# sticky-watch-v1_4.net
KiCad netlist of a schematic drawn in EAGLE
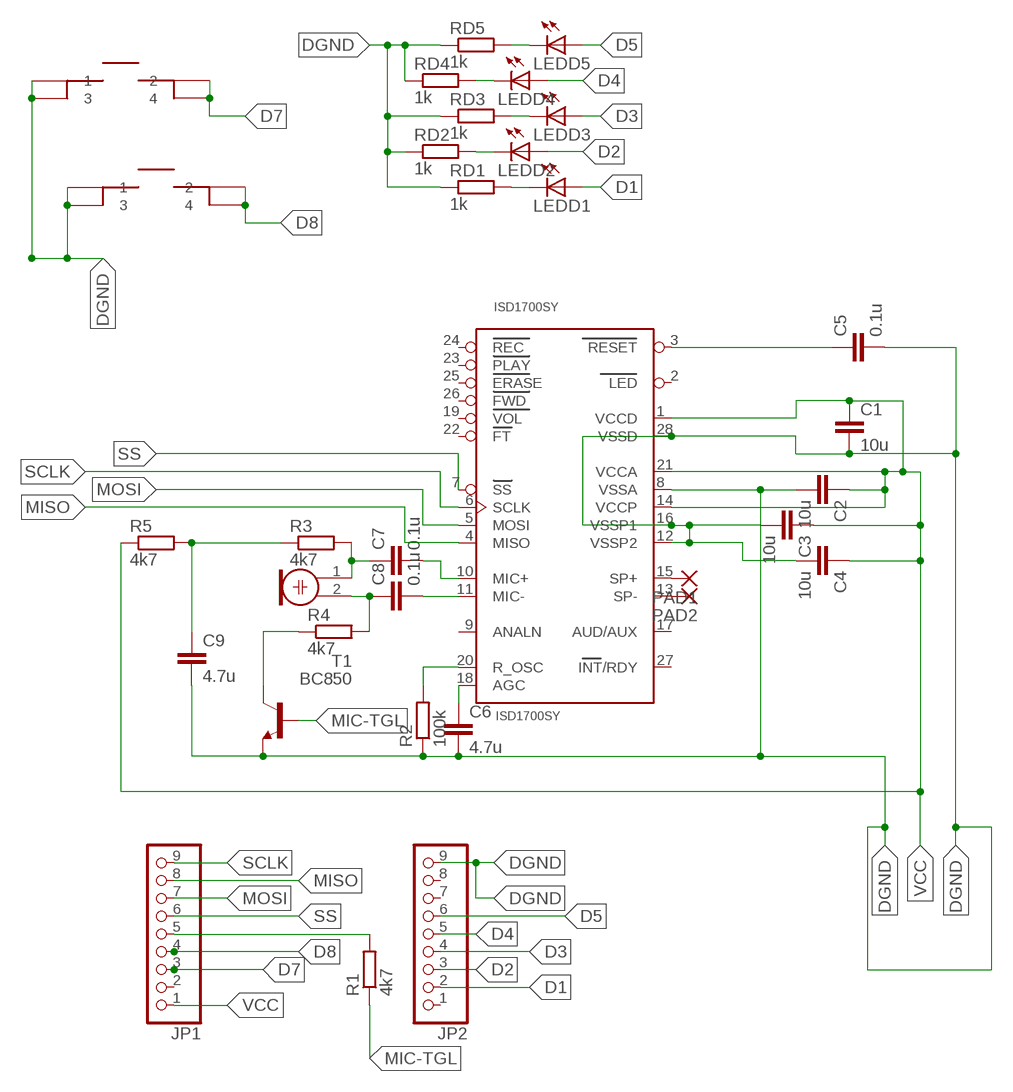
[diagram p0: schematic, sheet 1]

(export (version "E")
  (design (tool "Eeschema 10.0.6"))
  (components
    (comp (ref "C1")
      (value "10u")
      (footprint "eagle-import:C0603")
      (libsource (lib "eagle-import") (part "C-EUC0603"))
    )
    (comp (ref "C2")
      (value "10u")
      (footprint "eagle-import:C0603")
      (libsource (lib "eagle-import") (part "C-EUC0603"))
    )
    (comp (ref "C3")
      (value "10u")
      (footprint "eagle-import:C0603")
      (libsource (lib "eagle-import") (part "C-EUC0603"))
    )
    (comp (ref "C4")
      (value "10u")
      (footprint "eagle-import:C0603")
      (libsource (lib "eagle-import") (part "C-EUC0603"))
    )
    (comp (ref "C5")
      (value "0.1u")
      (footprint "eagle-import:C0603")
      (libsource (lib "eagle-import") (part "C-EUC0603"))
    )
    (comp (ref "C6")
      (value "4.7u")
      (footprint "eagle-import:C0603")
      (libsource (lib "eagle-import") (part "C-EUC0603"))
    )
    (comp (ref "C7")
      (value "0.1u")
      (footprint "eagle-import:C0603")
      (libsource (lib "eagle-import") (part "C-EUC0603"))
    )
    (comp (ref "C8")
      (value "0.1u")
      (footprint "eagle-import:C0603")
      (libsource (lib "eagle-import") (part "C-EUC0603"))
    )
    (comp (ref "C9")
      (value "4.7u")
      (footprint "eagle-import:C0603")
      (libsource (lib "eagle-import") (part "C-EUC0603"))
    )
    (comp (ref "ISD1700SY")
      (value "ISD1700SY")
      (footprint "eagle-import:SO28W")
      (libsource (lib "eagle-import") (part "ISD1700SY"))
    )
    (comp (ref "JP1")
      (value "PINHD-1X9")
      (footprint "eagle-import:1X09")
      (libsource (lib "eagle-import") (part "PINHD-1X9"))
    )
    (comp (ref "JP2")
      (value "PINHD-1X9")
      (footprint "eagle-import:1X09")
      (libsource (lib "eagle-import") (part "PINHD-1X9"))
    )
    (comp (ref "LEDD1")
      (value "LEDSML0805")
      (footprint "eagle-import:SML0805")
      (libsource (lib "eagle-import") (part "LEDSML0805"))
    )
    (comp (ref "LEDD2")
      (value "LEDSML0805")
      (footprint "eagle-import:SML0805")
      (libsource (lib "eagle-import") (part "LEDSML0805"))
    )
    (comp (ref "LEDD3")
      (value "LEDSML0805")
      (footprint "eagle-import:SML0805")
      (libsource (lib "eagle-import") (part "LEDSML0805"))
    )
    (comp (ref "LEDD4")
      (value "LEDSML0805")
      (footprint "eagle-import:SML0805")
      (libsource (lib "eagle-import") (part "LEDSML0805"))
    )
    (comp (ref "LEDD5")
      (value "LEDSML0805")
      (footprint "eagle-import:SML0805")
      (libsource (lib "eagle-import") (part "LEDSML0805"))
    )
    (comp (ref "M1")
      (value "ELECTRET_MICROPHON-WM-63PR")
      (footprint "eagle-import:WM-63PR")
      (libsource (lib "eagle-import") (part "ELECTRET_MICROPHON-WM-63PR"))
    )
    (comp (ref "PAD1")
      (value "1,6/0,8")
      (footprint "eagle-import:1,6_0,8")
      (libsource (lib "eagle-import") (part "1,6/0,8"))
    )
    (comp (ref "PAD2")
      (value "1,6/0,8")
      (footprint "eagle-import:1,6_0,8")
      (libsource (lib "eagle-import") (part "1,6/0,8"))
    )
    (comp (ref "R1")
      (value "4k7")
      (footprint "eagle-import:R0603")
      (libsource (lib "eagle-import") (part "R-EU_R0603"))
    )
    (comp (ref "R2")
      (value "100k")
      (footprint "eagle-import:R0603")
      (libsource (lib "eagle-import") (part "R-EU_R0603"))
    )
    (comp (ref "R3")
      (value "4k7")
      (footprint "eagle-import:R0603")
      (libsource (lib "eagle-import") (part "R-EU_R0603"))
    )
    (comp (ref "R4")
      (value "4k7")
      (footprint "eagle-import:R0603")
      (libsource (lib "eagle-import") (part "R-EU_R0603"))
    )
    (comp (ref "R5")
      (value "4k7")
      (footprint "eagle-import:R0603")
      (libsource (lib "eagle-import") (part "R-EU_R0603"))
    )
    (comp (ref "RD1")
      (value "1k")
      (footprint "eagle-import:R0603")
      (libsource (lib "eagle-import") (part "R-EU_R0603"))
    )
    (comp (ref "RD2")
      (value "1k")
      (footprint "eagle-import:R0603")
      (libsource (lib "eagle-import") (part "R-EU_R0603"))
    )
    (comp (ref "RD3")
      (value "1k")
      (footprint "eagle-import:R0603")
      (libsource (lib "eagle-import") (part "R-EU_R0603"))
    )
    (comp (ref "RD4")
      (value "1k")
      (footprint "eagle-import:R0603")
      (libsource (lib "eagle-import") (part "R-EU_R0603"))
    )
    (comp (ref "RD5")
      (value "1k")
      (footprint "eagle-import:R0603")
      (libsource (lib "eagle-import") (part "R-EU_R0603"))
    )
    (comp (ref "S1")
      (value "0")
      (footprint "eagle-import:SMD-TACT-5.2MM")
      (libsource (lib "eagle-import") (part "SMD-TACT"))
    )
    (comp (ref "S2")
      (value "SMD-TACT")
      (footprint "eagle-import:SMD-TACT-5.2MM")
      (libsource (lib "eagle-import") (part "SMD-TACT"))
    )
    (comp (ref "T1")
      (value "BC850")
      (footprint "eagle-import:SOT23")
      (libsource (lib "eagle-import") (part "BC850"))
    )
  )
  (nets
    (net (code "1") (name "D1") (class "Default")
      (node (ref "JP2") (pin "2") (pinfunction "2_2") (pintype "passive"))
      (node (ref "LEDD1") (pin "A") (pinfunction "A_A") (pintype "passive"))
    )
    (net (code "2") (name "D2") (class "Default")
      (node (ref "JP2") (pin "3") (pinfunction "3_3") (pintype "passive"))
      (node (ref "LEDD2") (pin "A") (pinfunction "A_A") (pintype "passive"))
    )
    (net (code "3") (name "D3") (class "Default")
      (node (ref "JP2") (pin "4") (pinfunction "4_4") (pintype "passive"))
      (node (ref "LEDD3") (pin "A") (pinfunction "A_A") (pintype "passive"))
    )
    (net (code "4") (name "D4") (class "Default")
      (node (ref "JP2") (pin "5") (pinfunction "5_5") (pintype "passive"))
      (node (ref "LEDD4") (pin "A") (pinfunction "A_A") (pintype "passive"))
    )
    (net (code "5") (name "D5") (class "Default")
      (node (ref "JP2") (pin "6") (pinfunction "6_6") (pintype "passive"))
      (node (ref "LEDD5") (pin "A") (pinfunction "A_A") (pintype "passive"))
    )
    (net (code "6") (name "D7") (class "Default")
      (node (ref "JP1") (pin "3") (pinfunction "3_3") (pintype "passive"))
      (node (ref "S2") (pin "2") (pinfunction "2_2") (pintype "bidirectional"))
      (node (ref "S2") (pin "4") (pinfunction "4_4") (pintype "bidirectional"))
    )
    (net (code "7") (name "D8") (class "Default")
      (node (ref "JP1") (pin "4") (pinfunction "4_4") (pintype "passive"))
      (node (ref "S1") (pin "2") (pinfunction "2_2") (pintype "bidirectional"))
      (node (ref "S1") (pin "4") (pinfunction "4_4") (pintype "bidirectional"))
    )
    (net (code "8") (name "DGND") (class "Default")
      (node (ref "C1") (pin "2") (pinfunction "2_2") (pintype "passive"))
      (node (ref "C2") (pin "2") (pinfunction "2_2") (pintype "passive"))
      (node (ref "C3") (pin "2") (pinfunction "2_2") (pintype "passive"))
      (node (ref "C4") (pin "2") (pinfunction "2_2") (pintype "passive"))
      (node (ref "C5") (pin "2") (pinfunction "2_2") (pintype "passive"))
      (node (ref "C6") (pin "2") (pinfunction "2_2") (pintype "passive"))
      (node (ref "C9") (pin "2") (pinfunction "2_2") (pintype "passive"))
      (node (ref "ISD1700SY") (pin "12") (pinfunction "VSSP2_12") (pintype "power_in"))
      (node (ref "ISD1700SY") (pin "16") (pinfunction "VSSP1_16") (pintype "power_in"))
      (node (ref "ISD1700SY") (pin "28") (pinfunction "VSSD_28") (pintype "power_in"))
      (node (ref "ISD1700SY") (pin "8") (pinfunction "VSSA_8") (pintype "power_in"))
      (node (ref "JP2") (pin "9") (pinfunction "9_9") (pintype "passive"))
      (node (ref "R2") (pin "1") (pinfunction "1_1") (pintype "passive"))
      (node (ref "RD1") (pin "1") (pinfunction "1_1") (pintype "passive"))
      (node (ref "RD2") (pin "1") (pinfunction "1_1") (pintype "passive"))
      (node (ref "RD3") (pin "1") (pinfunction "1_1") (pintype "passive"))
      (node (ref "RD4") (pin "1") (pinfunction "1_1") (pintype "passive"))
      (node (ref "RD5") (pin "1") (pinfunction "1_1") (pintype "passive"))
      (node (ref "S1") (pin "1") (pinfunction "1_1") (pintype "bidirectional"))
      (node (ref "S1") (pin "3") (pinfunction "3_3") (pintype "bidirectional"))
      (node (ref "S2") (pin "1") (pinfunction "1_1") (pintype "bidirectional"))
      (node (ref "S2") (pin "3") (pinfunction "3_3") (pintype "bidirectional"))
      (node (ref "T1") (pin "2") (pinfunction "E_2") (pintype "passive"))
    )
    (net (code "9") (name "MIC-TGL") (class "Default")
      (node (ref "R1") (pin "1") (pinfunction "1_1") (pintype "passive"))
      (node (ref "T1") (pin "1") (pinfunction "B_1") (pintype "passive"))
    )
    (net (code "10") (name "MISO") (class "Default")
      (node (ref "ISD1700SY") (pin "4") (pinfunction "MISO_4") (pintype "input"))
      (node (ref "JP1") (pin "8") (pinfunction "8_8") (pintype "passive"))
    )
    (net (code "11") (name "MOSI") (class "Default")
      (node (ref "ISD1700SY") (pin "5") (pinfunction "MOSI_5") (pintype "input"))
      (node (ref "JP1") (pin "7") (pinfunction "7_7") (pintype "passive"))
    )
    (net (code "12") (name "Net-(C7-Pad1)") (class "Default")
      (node (ref "C7") (pin "1") (pinfunction "1_1") (pintype "passive"))
      (node (ref "M1") (pin "1") (pinfunction "1_1") (pintype "passive"))
      (node (ref "R3") (pin "2") (pinfunction "2_2") (pintype "passive"))
    )
    (net (code "13") (name "Net-(C8-Pad1)") (class "Default")
      (node (ref "C8") (pin "1") (pinfunction "1_1") (pintype "passive"))
      (node (ref "M1") (pin "2") (pinfunction "2_2") (pintype "passive"))
      (node (ref "R4") (pin "2") (pinfunction "2_2") (pintype "passive"))
    )
    (net (code "14") (name "Net-(C9-Pad1)") (class "Default")
      (node (ref "C9") (pin "1") (pinfunction "1_1") (pintype "passive"))
      (node (ref "R3") (pin "1") (pinfunction "1_1") (pintype "passive"))
      (node (ref "R5") (pin "2") (pinfunction "2_2") (pintype "passive"))
    )
    (net (code "15") (name "Net-(ISD1700SY-AGC)") (class "Default")
      (node (ref "C6") (pin "1") (pinfunction "1_1") (pintype "passive"))
      (node (ref "ISD1700SY") (pin "18") (pinfunction "AGC_18") (pintype "passive"))
    )
    (net (code "16") (name "Net-(ISD1700SY-MIC+)") (class "Default")
      (node (ref "C7") (pin "2") (pinfunction "2_2") (pintype "passive"))
      (node (ref "ISD1700SY") (pin "10") (pinfunction "MIC+_10") (pintype "input"))
    )
    (net (code "17") (name "Net-(ISD1700SY-MIC-)") (class "Default")
      (node (ref "C8") (pin "2") (pinfunction "2_2") (pintype "passive"))
      (node (ref "ISD1700SY") (pin "11") (pinfunction "MIC-_11") (pintype "input"))
    )
    (net (code "18") (name "Net-(ISD1700SY-RESET)") (class "Default")
      (node (ref "C5") (pin "1") (pinfunction "1_1") (pintype "passive"))
      (node (ref "ISD1700SY") (pin "3") (pinfunction "RESET_3") (pintype "input"))
    )
    (net (code "19") (name "Net-(ISD1700SY-R_OSC)") (class "Default")
      (node (ref "ISD1700SY") (pin "20") (pinfunction "R_OSC_20") (pintype "passive"))
      (node (ref "R2") (pin "2") (pinfunction "2_2") (pintype "passive"))
    )
    (net (code "20") (name "Net-(ISD1700SY-SP+)") (class "Default")
      (node (ref "ISD1700SY") (pin "15") (pinfunction "SP+_15") (pintype "output"))
      (node (ref "PAD1") (pin "1") (pinfunction "P_1") (pintype "passive"))
    )
    (net (code "21") (name "Net-(ISD1700SY-SP-)") (class "Default")
      (node (ref "ISD1700SY") (pin "13") (pinfunction "SP-_13") (pintype "output"))
      (node (ref "PAD2") (pin "1") (pinfunction "P_1") (pintype "passive"))
    )
    (net (code "22") (name "Net-(JP1-Pad5)") (class "Default")
      (node (ref "JP1") (pin "5") (pinfunction "5_5") (pintype "passive"))
      (node (ref "R1") (pin "2") (pinfunction "2_2") (pintype "passive"))
    )
    (net (code "23") (name "Net-(LEDD1-PadC)") (class "Default")
      (node (ref "LEDD1") (pin "C") (pinfunction "C_C") (pintype "passive"))
      (node (ref "RD1") (pin "2") (pinfunction "2_2") (pintype "passive"))
    )
    (net (code "24") (name "Net-(LEDD2-PadC)") (class "Default")
      (node (ref "LEDD2") (pin "C") (pinfunction "C_C") (pintype "passive"))
      (node (ref "RD2") (pin "2") (pinfunction "2_2") (pintype "passive"))
    )
    (net (code "25") (name "Net-(LEDD3-PadC)") (class "Default")
      (node (ref "LEDD3") (pin "C") (pinfunction "C_C") (pintype "passive"))
      (node (ref "RD3") (pin "2") (pinfunction "2_2") (pintype "passive"))
    )
    (net (code "26") (name "Net-(LEDD4-PadC)") (class "Default")
      (node (ref "LEDD4") (pin "C") (pinfunction "C_C") (pintype "passive"))
      (node (ref "RD4") (pin "2") (pinfunction "2_2") (pintype "passive"))
    )
    (net (code "27") (name "Net-(LEDD5-PadC)") (class "Default")
      (node (ref "LEDD5") (pin "C") (pinfunction "C_C") (pintype "passive"))
      (node (ref "RD5") (pin "2") (pinfunction "2_2") (pintype "passive"))
    )
    (net (code "28") (name "Net-(T1-C)") (class "Default")
      (node (ref "R4") (pin "1") (pinfunction "1_1") (pintype "passive"))
      (node (ref "T1") (pin "3") (pinfunction "C_3") (pintype "passive"))
    )
    (net (code "29") (name "SCLK") (class "Default")
      (node (ref "ISD1700SY") (pin "6") (pinfunction "SCLK_6") (pintype "input"))
      (node (ref "JP1") (pin "9") (pinfunction "9_9") (pintype "passive"))
    )
    (net (code "30") (name "SS") (class "Default")
      (node (ref "ISD1700SY") (pin "7") (pinfunction "SS_7") (pintype "input"))
      (node (ref "JP1") (pin "6") (pinfunction "6_6") (pintype "passive"))
    )
    (net (code "31") (name "VCC") (class "Default")
      (node (ref "C1") (pin "1") (pinfunction "1_1") (pintype "passive"))
      (node (ref "C2") (pin "1") (pinfunction "1_1") (pintype "passive"))
      (node (ref "C3") (pin "1") (pinfunction "1_1") (pintype "passive"))
      (node (ref "C4") (pin "1") (pinfunction "1_1") (pintype "passive"))
      (node (ref "ISD1700SY") (pin "1") (pinfunction "VCCD_1") (pintype "power_in"))
      (node (ref "ISD1700SY") (pin "14") (pinfunction "VCCP_14") (pintype "power_in"))
      (node (ref "ISD1700SY") (pin "21") (pinfunction "VCCA_21") (pintype "power_in"))
      (node (ref "JP1") (pin "1") (pinfunction "1_1") (pintype "passive"))
      (node (ref "R5") (pin "1") (pinfunction "1_1") (pintype "passive"))
    )
    (net (code "32") (name "unconnected-(ISD1700SY-ANALN-Pad9)") (class "Default")
      (node (ref "ISD1700SY") (pin "9") (pinfunction "ANALN_9") (pintype "input"))
    )
    (net (code "33") (name "unconnected-(ISD1700SY-AUD{slash}AUX-Pad17)") (class "Default")
      (node (ref "ISD1700SY") (pin "17") (pinfunction "AUD/AUX_17") (pintype "output"))
    )
    (net (code "34") (name "unconnected-(ISD1700SY-ERASE-Pad25)") (class "Default")
      (node (ref "ISD1700SY") (pin "25") (pinfunction "ERASE_25") (pintype "input"))
    )
    (net (code "35") (name "unconnected-(ISD1700SY-FT-Pad22)") (class "Default")
      (node (ref "ISD1700SY") (pin "22") (pinfunction "FT_22") (pintype "input"))
    )
    (net (code "36") (name "unconnected-(ISD1700SY-FWD-Pad26)") (class "Default")
      (node (ref "ISD1700SY") (pin "26") (pinfunction "FWD_26") (pintype "input"))
    )
    (net (code "37") (name "unconnected-(ISD1700SY-INT{slash}RDY-Pad27)") (class "Default")
      (node (ref "ISD1700SY") (pin "27") (pinfunction "INT/RDY_27") (pintype "bidirectional"))
    )
    (net (code "38") (name "unconnected-(ISD1700SY-LED-Pad2)") (class "Default")
      (node (ref "ISD1700SY") (pin "2") (pinfunction "LED_2") (pintype "input"))
    )
    (net (code "39") (name "unconnected-(ISD1700SY-PLAY-Pad23)") (class "Default")
      (node (ref "ISD1700SY") (pin "23") (pinfunction "PLAY_23") (pintype "input"))
    )
    (net (code "40") (name "unconnected-(ISD1700SY-REC-Pad24)") (class "Default")
      (node (ref "ISD1700SY") (pin "24") (pinfunction "REC_24") (pintype "input"))
    )
    (net (code "41") (name "unconnected-(ISD1700SY-VOL-Pad19)") (class "Default")
      (node (ref "ISD1700SY") (pin "19") (pinfunction "VOL_19") (pintype "input"))
    )
    (net (code "42") (name "unconnected-(JP1-Pad2)") (class "Default")
      (node (ref "JP1") (pin "2") (pinfunction "2_2") (pintype "passive"))
    )
    (net (code "43") (name "unconnected-(JP2-Pad1)") (class "Default")
      (node (ref "JP2") (pin "1") (pinfunction "1_1") (pintype "passive"))
    )
    (net (code "44") (name "unconnected-(JP2-Pad7)") (class "Default")
      (node (ref "JP2") (pin "7") (pinfunction "7_7") (pintype "passive"))
    )
    (net (code "45") (name "unconnected-(JP2-Pad8)") (class "Default")
      (node (ref "JP2") (pin "8") (pinfunction "8_8") (pintype "passive"))
    )
  )
)
